# PGA.net
KiCad netlist of a schematic drawn in Altium Designer
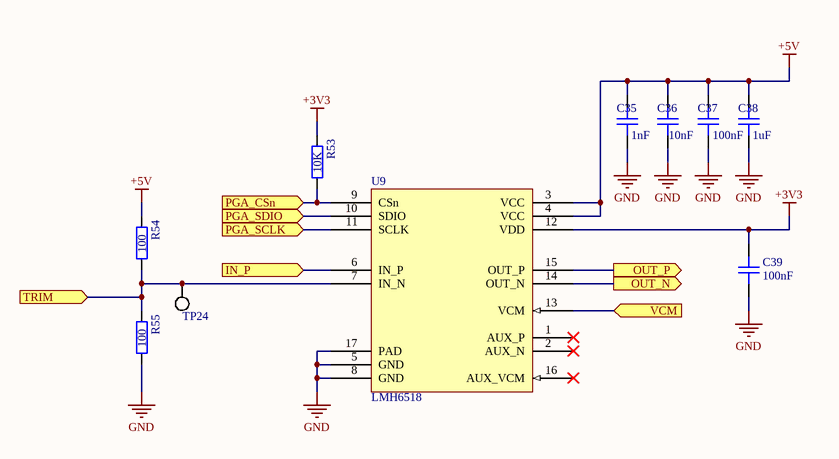
[diagram p0: PGA.SchDoc]

(export (version "E")
  (design (tool "Eeschema 10.0.6"))
  (components
    (comp (ref "C35")
      (value "1nF")
      (footprint "GEN_C_0402")
      (libsource (lib "DSO") (part "CAP 1nF 50V C0G 0402"))
    )
    (comp (ref "C36")
      (value "10nF")
      (footprint "GEN_C_0402")
      (libsource (lib "DSO") (part "CAP 10nF 50V X7R 0402"))
    )
    (comp (ref "C37")
      (value "100nF")
      (footprint "GEN_C_0402")
      (libsource (lib "DSO") (part "CAP 100nF 16V X7R 0402"))
    )
    (comp (ref "C38")
      (value "1uF")
      (footprint "GEN_C_0402")
      (libsource (lib "DSO") (part "CAP 1uF 25V X5R 0402"))
    )
    (comp (ref "C39")
      (value "100nF")
      (footprint "GEN_C_0402")
      (libsource (lib "DSO") (part "CAP 100nF 16V X7R 0402"))
    )
    (comp (ref "R53")
      (value "10K")
      (footprint "GEN_R_0402")
      (fields (field (name "TOLERANCE") "1%"))
      (libsource (lib "DSO") (part "RES 10K OHM 1% 1/10W 0402"))
    )
    (comp (ref "R54")
      (value "100")
      (footprint "GEN_R_0402")
      (fields (field (name "TOLERANCE") "1%"))
      (libsource (lib "DSO") (part "RES 100 OHM 1% 1/10W 0402"))
    )
    (comp (ref "R55")
      (value "100")
      (footprint "GEN_R_0402")
      (fields (field (name "TOLERANCE") "1%"))
      (libsource (lib "DSO") (part "RES 100 OHM 1% 1/10W 0402"))
    )
    (comp (ref "TP24") (value "PCB") (footprint "GEN_TP_PCB") (libsource (lib "DSO") (part "TP PCB 1mm")))
    (comp (ref "U9")
      (value "LMH6518")
      (footprint "TI_WQFN_RGH0016A")
      (libsource (lib "DSO") (part "IC PGA LMH6518"))
    )
  )
  (nets
    (net (code "1") (name "+3V3") (class "Default")
      (node (ref "C39") (pin "2") (pinfunction "2_2") (pintype "passive"))
      (node (ref "R53") (pin "2") (pinfunction "2_2") (pintype "passive"))
      (node (ref "U9") (pin "12") (pinfunction "VDD_12") (pintype "power_in"))
    )
    (net (code "2") (name "+5V") (class "Default")
      (node (ref "C35") (pin "2") (pinfunction "2_2") (pintype "passive"))
      (node (ref "C36") (pin "2") (pinfunction "2_2") (pintype "passive"))
      (node (ref "C37") (pin "2") (pinfunction "2_2") (pintype "passive"))
      (node (ref "C38") (pin "2") (pinfunction "2_2") (pintype "passive"))
      (node (ref "R54") (pin "2") (pinfunction "2_2") (pintype "passive"))
      (node (ref "U9") (pin "3") (pinfunction "VCC_3") (pintype "power_in"))
      (node (ref "U9") (pin "4") (pinfunction "VCC_4") (pintype "power_in"))
    )
    (net (code "3") (name "/IN_P") (class "Default")
      (node (ref "U9") (pin "6") (pinfunction "IN_P_6") (pintype "passive"))
    )
    (net (code "4") (name "/OUT_N") (class "Default")
      (node (ref "U9") (pin "14") (pinfunction "OUT_N_14") (pintype "passive"))
    )
    (net (code "5") (name "/OUT_P") (class "Default")
      (node (ref "U9") (pin "15") (pinfunction "OUT_P_15") (pintype "passive"))
    )
    (net (code "6") (name "/PGA_CSn") (class "Default")
      (node (ref "R53") (pin "1") (pinfunction "1_1") (pintype "passive"))
      (node (ref "U9") (pin "9") (pinfunction "CSn_9") (pintype "passive"))
    )
    (net (code "7") (name "/PGA_SCLK") (class "Default")
      (node (ref "U9") (pin "11") (pinfunction "SCLK_11") (pintype "passive"))
    )
    (net (code "8") (name "/PGA_SDIO") (class "Default")
      (node (ref "U9") (pin "10") (pinfunction "SDIO_10") (pintype "passive"))
    )
    (net (code "9") (name "/TRIM") (class "Default")
      (node (ref "R54") (pin "1") (pinfunction "1_1") (pintype "passive"))
      (node (ref "R55") (pin "2") (pinfunction "2_2") (pintype "passive"))
      (node (ref "TP24") (pin "1") (pinfunction "1_1") (pintype "passive"))
      (node (ref "U9") (pin "7") (pinfunction "IN_N_7") (pintype "passive"))
    )
    (net (code "10") (name "/VCM") (class "Default")
      (node (ref "U9") (pin "13") (pinfunction "VCM_13") (pintype "input"))
    )
    (net (code "11") (name "GND") (class "Default")
      (node (ref "C35") (pin "1") (pinfunction "1_1") (pintype "passive"))
      (node (ref "C36") (pin "1") (pinfunction "1_1") (pintype "passive"))
      (node (ref "C37") (pin "1") (pinfunction "1_1") (pintype "passive"))
      (node (ref "C38") (pin "1") (pinfunction "1_1") (pintype "passive"))
      (node (ref "C39") (pin "1") (pinfunction "1_1") (pintype "passive"))
      (node (ref "R55") (pin "1") (pinfunction "1_1") (pintype "passive"))
      (node (ref "U9") (pin "17") (pinfunction "PAD_17") (pintype "power_in"))
      (node (ref "U9") (pin "5") (pinfunction "GND_5") (pintype "power_in"))
      (node (ref "U9") (pin "8") (pinfunction "GND_8") (pintype "power_in"))
    )
    (net (code "12") (name "unconnected-(U9-AUX_N-Pad2)") (class "Default")
      (node (ref "U9") (pin "2") (pinfunction "AUX_N_2") (pintype "passive+no_connect"))
    )
    (net (code "13") (name "unconnected-(U9-AUX_P-Pad1)") (class "Default")
      (node (ref "U9") (pin "1") (pinfunction "AUX_P_1") (pintype "passive+no_connect"))
    )
    (net (code "14") (name "unconnected-(U9-AUX_VCM-Pad16)") (class "Default")
      (node (ref "U9") (pin "16") (pinfunction "AUX_VCM_16") (pintype "input+no_connect"))
    )
  )
)
